# design.net
KiCad netlist of a schematic drawn in Altium Designer
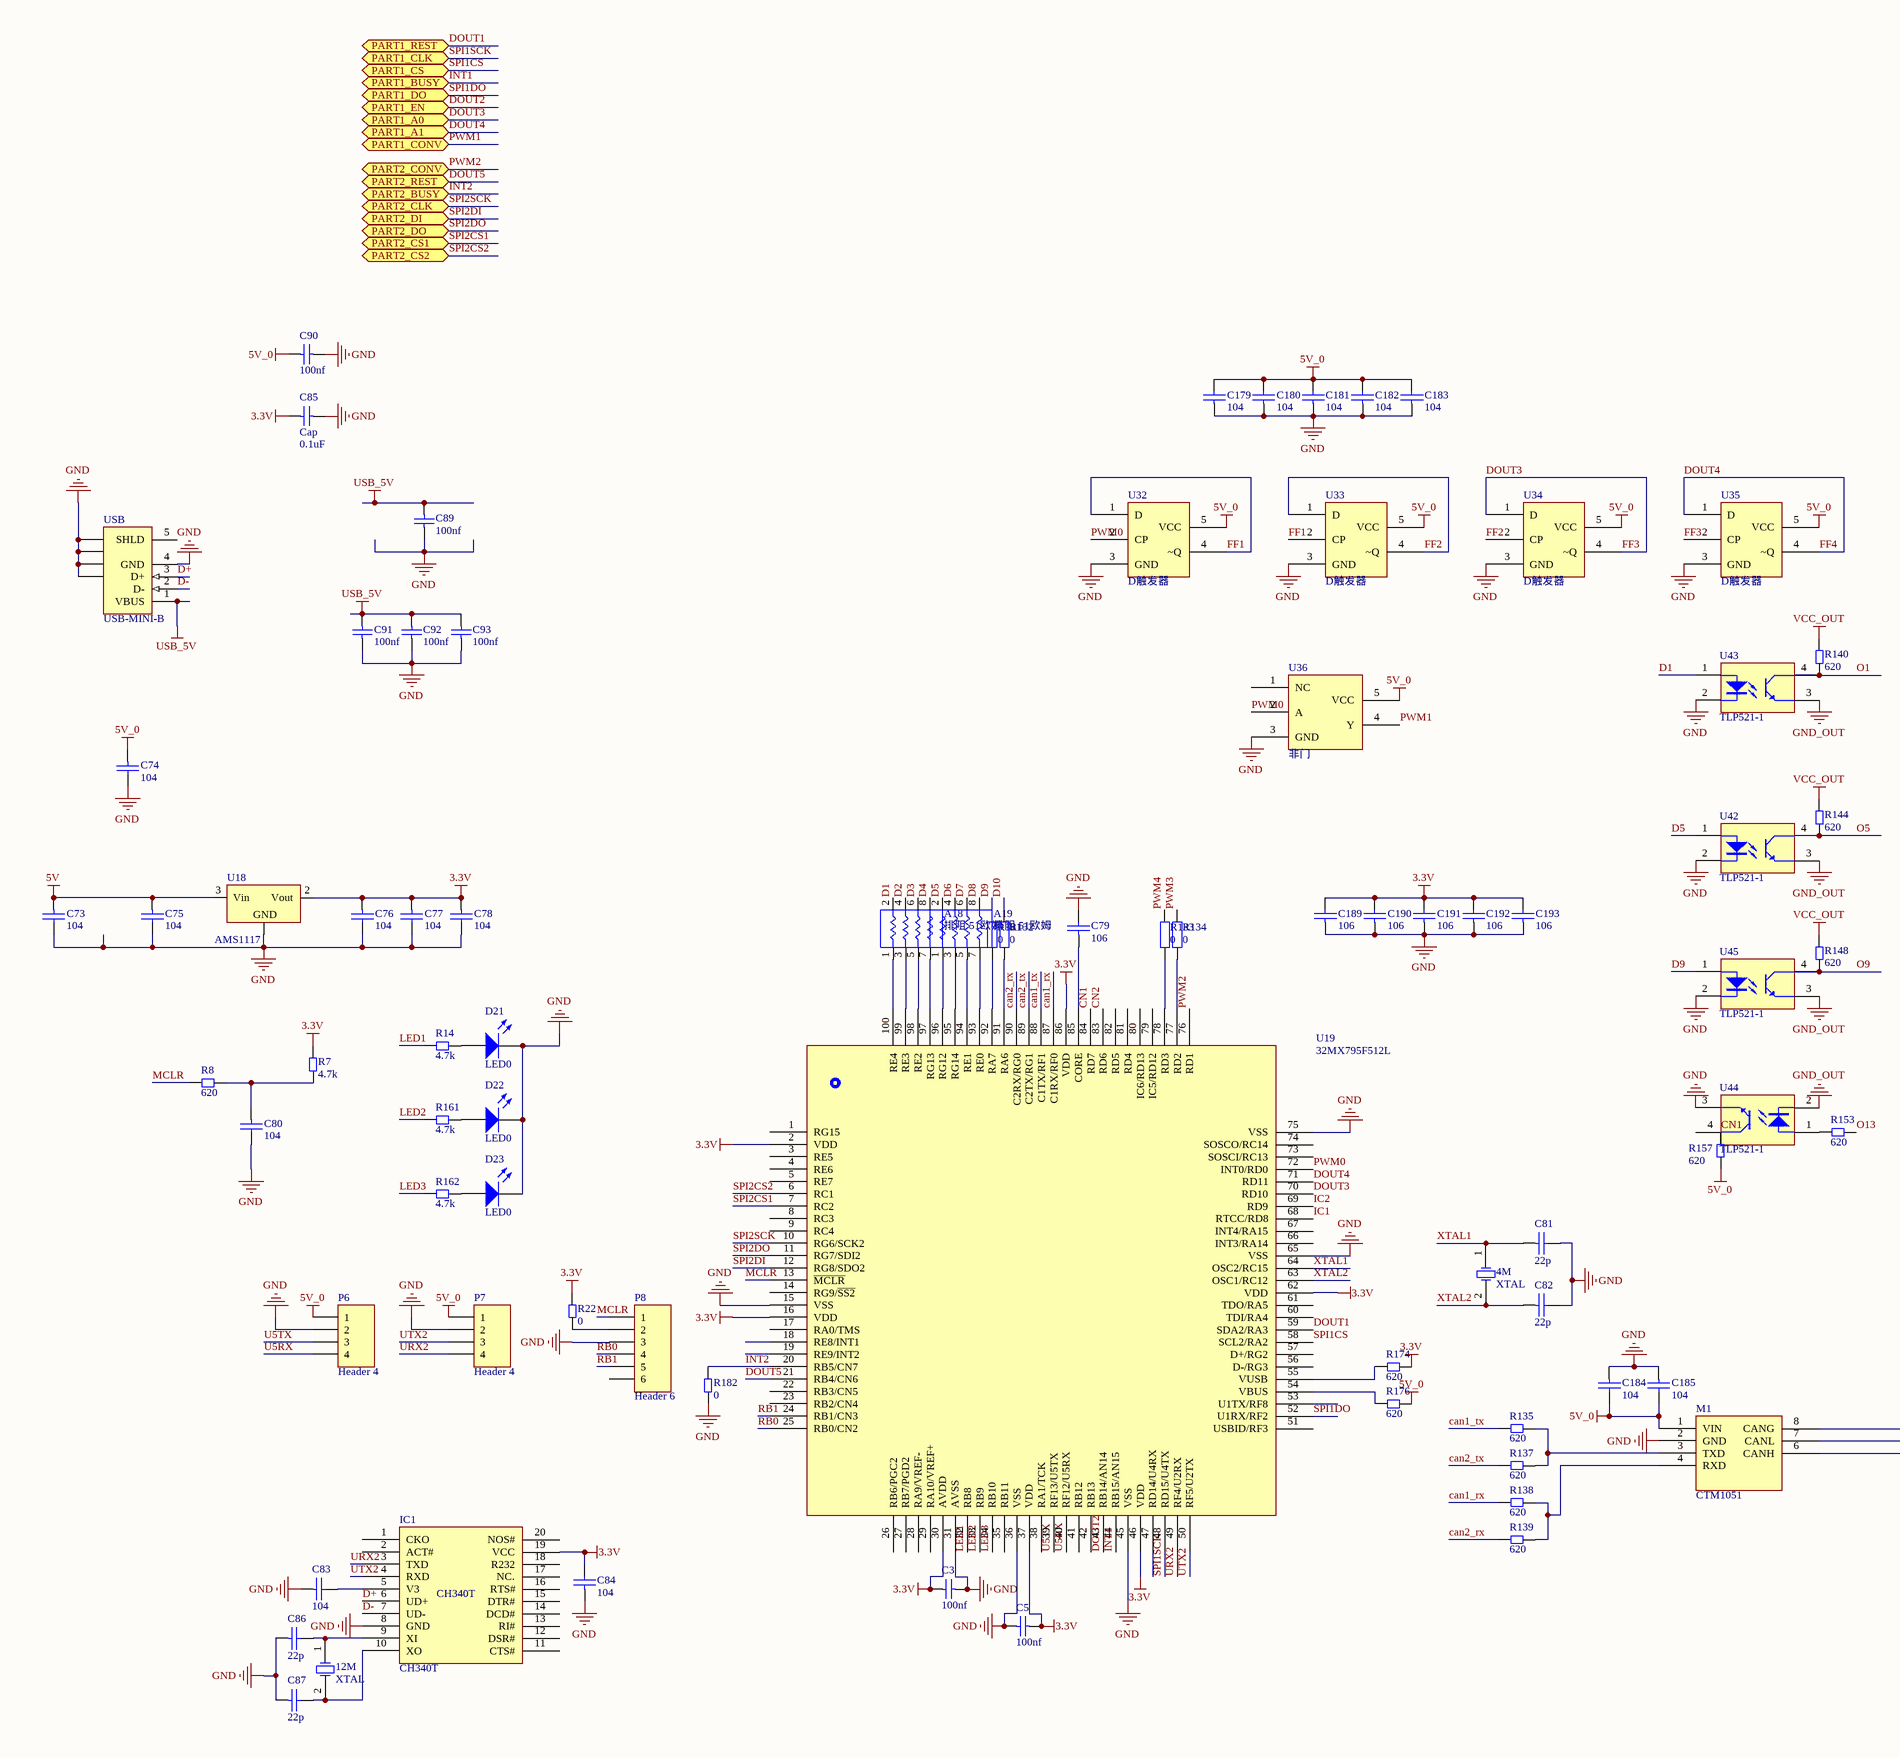
[diagram p0: 数字部分.SchDoc, left]
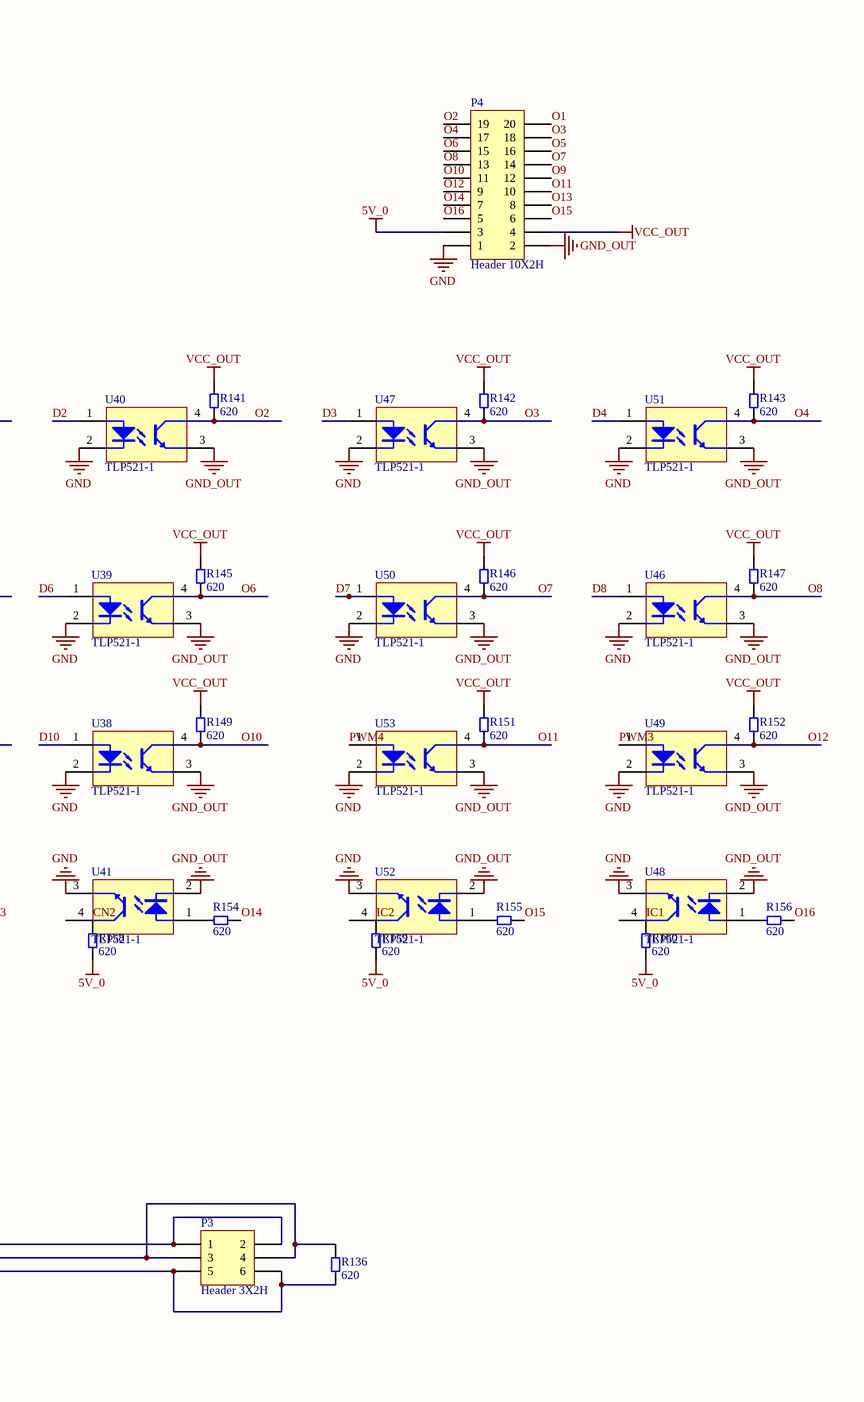
[diagram p1: 数字部分.SchDoc, right]

(export (version "E")
  (design (tool "Eeschema 10.0.6"))
  (components
    (comp (ref "4M")
      (value "XTAL")
      (footprint "5032-xtal")
      (description "Crystal Oscillator")
      (fields (field (name "PUBLISHER") "Altium Limited"))
      (libsource (lib "Miscellaneous Devices") (part "XTAL"))
    )
    (comp (ref "12M")
      (value "XTAL")
      (footprint "5032-xtal")
      (description "Crystal Oscillator")
      (fields (field (name "PUBLISHER") "Altium Limited"))
      (libsource (lib "Miscellaneous Devices") (part "XTAL"))
    )
    (comp (ref "A18")
      (value "排阻 51欧姆")
      (footprint "RCA03-4D")
      (libsource (lib "AD7606V23A") (part "RESPACK5"))
    )
    (comp (ref "A19")
      (value "排阻 51欧姆")
      (footprint "RCA03-4D")
      (libsource (lib "AD7606V23A") (part "RESPACK5"))
    )
    (comp (ref "C3")
      (value "100nf")
      (footprint "0805C")
      (description "Capacitor")
      (fields (field (name "Comment") "Cap") (field (name "PUBLISHER") "Altium Limited"))
      (libsource (lib "Miscellaneous Devices") (part "Cap"))
    )
    (comp (ref "C5")
      (value "100nf")
      (footprint "0805C")
      (description "Capacitor")
      (fields (field (name "Comment") "Cap") (field (name "PUBLISHER") "Altium Limited"))
      (libsource (lib "Miscellaneous Devices") (part "Cap"))
    )
    (comp (ref "C73")
      (value "104")
      (footprint "0805C")
      (description "Capacitor")
      (libsource (lib "Miscellaneous Devices") (part "CAP"))
    )
    (comp (ref "C74")
      (value "104")
      (footprint "0805C")
      (description "Capacitor")
      (libsource (lib "Miscellaneous Devices") (part "CAP"))
    )
    (comp (ref "C75")
      (value "104")
      (footprint "0805C")
      (description "Capacitor")
      (libsource (lib "Miscellaneous Devices") (part "CAP"))
    )
    (comp (ref "C76")
      (value "104")
      (footprint "0805C")
      (description "Capacitor")
      (libsource (lib "Miscellaneous Devices") (part "CAP"))
    )
    (comp (ref "C77")
      (value "104")
      (footprint "0805C")
      (description "Capacitor")
      (libsource (lib "Miscellaneous Devices") (part "CAP"))
    )
    (comp (ref "C78")
      (value "104")
      (footprint "0805C")
      (description "Capacitor")
      (libsource (lib "Miscellaneous Devices") (part "CAP"))
    )
    (comp (ref "C79")
      (value "106")
      (footprint "0805C")
      (description "Capacitor")
      (libsource (lib "Miscellaneous Devices") (part "CAP"))
    )
    (comp (ref "C80")
      (value "104")
      (footprint "0805C")
      (description "Capacitor")
      (libsource (lib "Miscellaneous Devices") (part "CAP"))
    )
    (comp (ref "C81")
      (value "22p")
      (footprint "0805C")
      (description "Capacitor")
      (libsource (lib "Miscellaneous Devices") (part "CAP"))
    )
    (comp (ref "C82")
      (value "22p")
      (footprint "0805C")
      (description "Capacitor")
      (libsource (lib "Miscellaneous Devices") (part "CAP"))
    )
    (comp (ref "C83")
      (value "104")
      (footprint "0805C")
      (description "Capacitor")
      (libsource (lib "Miscellaneous Devices") (part "CAP"))
    )
    (comp (ref "C84")
      (value "104")
      (footprint "0805C")
      (description "Capacitor")
      (libsource (lib "Miscellaneous Devices") (part "CAP"))
    )
    (comp (ref "C85")
      (value "Cap")
      (footprint "0805C")
      (description "Capacitor (Semiconductor SIM Model)")
      (fields (field (name "ALTIUM_VALUE") "0.1uF") (field (name "PUBLISHER") "Altium Limited"))
      (libsource (lib "Miscellaneous Devices") (part "Cap Semi"))
    )
    (comp (ref "C86")
      (value "22p")
      (footprint "0805C")
      (description "Capacitor")
      (libsource (lib "Miscellaneous Devices") (part "CAP"))
    )
    (comp (ref "C87")
      (value "22p")
      (footprint "0805C")
      (description "Capacitor")
      (libsource (lib "Miscellaneous Devices") (part "CAP"))
    )
    (comp (ref "C89")
      (value "100nf")
      (footprint "1812-C")
      (description "Capacitor")
      (fields (field (name "Comment") "Cap") (field (name "PUBLISHER") "Altium Limited"))
      (libsource (lib "Miscellaneous Devices") (part "Cap"))
    )
    (comp (ref "C90")
      (value "100nf")
      (footprint "0805C")
      (description "Capacitor")
      (fields (field (name "Comment") "Cap") (field (name "PUBLISHER") "Altium Limited"))
      (libsource (lib "Miscellaneous Devices") (part "Cap"))
    )
    (comp (ref "C91")
      (value "100nf")
      (footprint "0805C")
      (description "Capacitor")
      (fields (field (name "Comment") "Cap") (field (name "PUBLISHER") "Altium Limited"))
      (libsource (lib "Miscellaneous Devices") (part "Cap"))
    )
    (comp (ref "C92")
      (value "100nf")
      (footprint "0805C")
      (description "Capacitor")
      (fields (field (name "Comment") "Cap") (field (name "PUBLISHER") "Altium Limited"))
      (libsource (lib "Miscellaneous Devices") (part "Cap"))
    )
    (comp (ref "C93")
      (value "100nf")
      (footprint "0805C")
      (description "Capacitor")
      (fields (field (name "Comment") "Cap") (field (name "PUBLISHER") "Altium Limited"))
      (libsource (lib "Miscellaneous Devices") (part "Cap"))
    )
    (comp (ref "C179")
      (value "104")
      (footprint "0805C")
      (description "Capacitor")
      (libsource (lib "Miscellaneous Devices") (part "CAP"))
    )
    (comp (ref "C180")
      (value "104")
      (footprint "0805C")
      (description "Capacitor")
      (libsource (lib "Miscellaneous Devices") (part "CAP"))
    )
    (comp (ref "C181")
      (value "104")
      (footprint "0805C")
      (description "Capacitor")
      (libsource (lib "Miscellaneous Devices") (part "CAP"))
    )
    (comp (ref "C182")
      (value "104")
      (footprint "0805C")
      (description "Capacitor")
      (libsource (lib "Miscellaneous Devices") (part "CAP"))
    )
    (comp (ref "C183")
      (value "104")
      (footprint "0805C")
      (description "Capacitor")
      (libsource (lib "Miscellaneous Devices") (part "CAP"))
    )
    (comp (ref "C184")
      (value "104")
      (footprint "0805C")
      (description "Capacitor")
      (libsource (lib "Miscellaneous Devices") (part "CAP"))
    )
    (comp (ref "C185")
      (value "104")
      (footprint "0805C")
      (description "Capacitor")
      (libsource (lib "Miscellaneous Devices") (part "CAP"))
    )
    (comp (ref "C189")
      (value "106")
      (footprint "0805C")
      (description "Capacitor")
      (libsource (lib "Miscellaneous Devices") (part "CAP"))
    )
    (comp (ref "C190")
      (value "106")
      (footprint "0805C")
      (description "Capacitor")
      (libsource (lib "Miscellaneous Devices") (part "CAP"))
    )
    (comp (ref "C191")
      (value "106")
      (footprint "0805C")
      (description "Capacitor")
      (libsource (lib "Miscellaneous Devices") (part "CAP"))
    )
    (comp (ref "C192")
      (value "106")
      (footprint "0805C")
      (description "Capacitor")
      (libsource (lib "Miscellaneous Devices") (part "CAP"))
    )
    (comp (ref "C193")
      (value "106")
      (footprint "0805C")
      (description "Capacitor")
      (libsource (lib "Miscellaneous Devices") (part "CAP"))
    )
    (comp (ref "D21")
      (value "LED0")
      (footprint "0805C")
      (description "Typical INFRARED GaAs LED")
      (fields (field (name "PUBLISHER") "Altium Limited"))
      (libsource (lib "Miscellaneous Devices") (part "LED0"))
    )
    (comp (ref "D22")
      (value "LED0")
      (footprint "0805C")
      (description "Typical INFRARED GaAs LED")
      (fields (field (name "PUBLISHER") "Altium Limited"))
      (libsource (lib "Miscellaneous Devices") (part "LED0"))
    )
    (comp (ref "D23")
      (value "LED0")
      (footprint "0805C")
      (description "Typical INFRARED GaAs LED")
      (fields (field (name "PUBLISHER") "Altium Limited"))
      (libsource (lib "Miscellaneous Devices") (part "LED0"))
    )
    (comp (ref "IC1") (value "CH340T") (footprint "TSSOP20") (libsource (lib "ic_lib") (part "CH340T")))
    (comp (ref "M1") (value "CTM1051") (footprint "CTM1051") (libsource (lib "ic_lib") (part "CTM1051")))
    (comp (ref "P3")
      (value "Header 3X2H")
      (footprint "3.81MM-3P*2")
      (description "Header, 3-Pin, Dual row, Right Angle")
      (fields (field (name "PUBLISHER") "Altium Limited"))
      (libsource (lib "Miscellaneous Connectors") (part "Header 3X2H"))
    )
    (comp (ref "P4")
      (value "Header 10X2H")
      (footprint "20P牛角")
      (description "Header, 10-Pin, Dual row, Right Angle")
      (fields (field (name "PUBLISHER") "Altium Limited"))
      (libsource (lib "Miscellaneous Connectors") (part "Header 10X2H"))
    )
    (comp (ref "P6")
      (value "Header 4")
      (footprint "PH2.0 D-L-4P")
      (description "Header, 4-Pin")
      (fields (field (name "PUBLISHER") "Altium Limited"))
      (libsource (lib "Miscellaneous Connectors") (part "Header 4"))
    )
    (comp (ref "P7")
      (value "Header 4")
      (footprint "PH2.0 D-L-4P")
      (description "Header, 4-Pin")
      (fields (field (name "PUBLISHER") "Altium Limited"))
      (libsource (lib "Miscellaneous Connectors") (part "Header 4"))
    )
    (comp (ref "P8")
      (value "Header 6")
      (footprint "PH2.0 D-L-6P")
      (description "Header, 6-Pin")
      (fields (field (name "PUBLISHER") "Altium Limited"))
      (libsource (lib "Miscellaneous Connectors") (part "Header 6"))
    )
    (comp (ref "R7")
      (value "4.7k")
      (footprint "0805R")
      (libsource (lib "Miscellaneous Devices") (part "RES2"))
    )
    (comp (ref "R8")
      (value "620")
      (footprint "0805R")
      (libsource (lib "Miscellaneous Devices") (part "RES2"))
    )
    (comp (ref "R14")
      (value "4.7k")
      (footprint "0805R")
      (libsource (lib "Miscellaneous Devices") (part "RES2"))
    )
    (comp (ref "R22") (value "0") (footprint "0805R") (libsource (lib "Miscellaneous Devices") (part "RES2")))
    (comp (ref "R131")
      (value "0")
      (footprint "0603AR")
      (description "Resistor")
      (fields (field (name "Comment") "Res2") (field (name "PUBLISHER") "Altium Limited"))
      (libsource (lib "Miscellaneous Devices") (part "Res2"))
    )
    (comp (ref "R132")
      (value "0")
      (footprint "0603AR")
      (description "Resistor")
      (fields (field (name "Comment") "Res2") (field (name "PUBLISHER") "Altium Limited"))
      (libsource (lib "Miscellaneous Devices") (part "Res2"))
    )
    (comp (ref "R133")
      (value "0")
      (footprint "0603AR")
      (description "Resistor")
      (fields (field (name "Comment") "Res2") (field (name "PUBLISHER") "Altium Limited"))
      (libsource (lib "Miscellaneous Devices") (part "Res2"))
    )
    (comp (ref "R134")
      (value "0")
      (footprint "0603AR")
      (description "Resistor")
      (fields (field (name "Comment") "Res2") (field (name "PUBLISHER") "Altium Limited"))
      (libsource (lib "Miscellaneous Devices") (part "Res2"))
    )
    (comp (ref "R135")
      (value "620")
      (footprint "0805R")
      (libsource (lib "Miscellaneous Devices") (part "RES2"))
    )
    (comp (ref "R136")
      (value "620")
      (footprint "FB1206")
      (libsource (lib "Miscellaneous Devices") (part "RES2"))
    )
    (comp (ref "R137")
      (value "620")
      (footprint "0805R")
      (libsource (lib "Miscellaneous Devices") (part "RES2"))
    )
    (comp (ref "R138")
      (value "620")
      (footprint "0805R")
      (libsource (lib "Miscellaneous Devices") (part "RES2"))
    )
    (comp (ref "R139")
      (value "620")
      (footprint "0805R")
      (libsource (lib "Miscellaneous Devices") (part "RES2"))
    )
    (comp (ref "R140")
      (value "620")
      (footprint "0805R")
      (libsource (lib "Miscellaneous Devices") (part "RES2"))
    )
    (comp (ref "R141")
      (value "620")
      (footprint "0805R")
      (libsource (lib "Miscellaneous Devices") (part "RES2"))
    )
    (comp (ref "R142")
      (value "620")
      (footprint "0805R")
      (libsource (lib "Miscellaneous Devices") (part "RES2"))
    )
    (comp (ref "R143")
      (value "620")
      (footprint "0805R")
      (libsource (lib "Miscellaneous Devices") (part "RES2"))
    )
    (comp (ref "R144")
      (value "620")
      (footprint "0805R")
      (libsource (lib "Miscellaneous Devices") (part "RES2"))
    )
    (comp (ref "R145")
      (value "620")
      (footprint "0805R")
      (libsource (lib "Miscellaneous Devices") (part "RES2"))
    )
    (comp (ref "R146")
      (value "620")
      (footprint "0805R")
      (libsource (lib "Miscellaneous Devices") (part "RES2"))
    )
    (comp (ref "R147")
      (value "620")
      (footprint "0805R")
      (libsource (lib "Miscellaneous Devices") (part "RES2"))
    )
    (comp (ref "R148")
      (value "620")
      (footprint "0805R")
      (libsource (lib "Miscellaneous Devices") (part "RES2"))
    )
    (comp (ref "R149")
      (value "620")
      (footprint "0805R")
      (libsource (lib "Miscellaneous Devices") (part "RES2"))
    )
    (comp (ref "R151")
      (value "620")
      (footprint "0805R")
      (libsource (lib "Miscellaneous Devices") (part "RES2"))
    )
    (comp (ref "R152")
      (value "620")
      (footprint "0805R")
      (libsource (lib "Miscellaneous Devices") (part "RES2"))
    )
    (comp (ref "R153")
      (value "620")
      (footprint "0805R")
      (libsource (lib "Miscellaneous Devices") (part "RES2"))
    )
    (comp (ref "R154")
      (value "620")
      (footprint "0805R")
      (libsource (lib "Miscellaneous Devices") (part "RES2"))
    )
    (comp (ref "R155")
      (value "620")
      (footprint "0805R")
      (libsource (lib "Miscellaneous Devices") (part "RES2"))
    )
    (comp (ref "R156")
      (value "620")
      (footprint "0805R")
      (libsource (lib "Miscellaneous Devices") (part "RES2"))
    )
    (comp (ref "R157")
      (value "620")
      (footprint "0805R")
      (libsource (lib "Miscellaneous Devices") (part "RES2"))
    )
    (comp (ref "R158")
      (value "620")
      (footprint "0805R")
      (libsource (lib "Miscellaneous Devices") (part "RES2"))
    )
    (comp (ref "R159")
      (value "620")
      (footprint "0805R")
      (libsource (lib "Miscellaneous Devices") (part "RES2"))
    )
    (comp (ref "R160")
      (value "620")
      (footprint "0805R")
      (libsource (lib "Miscellaneous Devices") (part "RES2"))
    )
    (comp (ref "R161")
      (value "4.7k")
      (footprint "0805R")
      (libsource (lib "Miscellaneous Devices") (part "RES2"))
    )
    (comp (ref "R162")
      (value "4.7k")
      (footprint "0805R")
      (libsource (lib "Miscellaneous Devices") (part "RES2"))
    )
    (comp (ref "R174")
      (value "620")
      (footprint "0805R")
      (libsource (lib "Miscellaneous Devices") (part "RES2"))
    )
    (comp (ref "R176")
      (value "620")
      (footprint "0805R")
      (libsource (lib "Miscellaneous Devices") (part "RES2"))
    )
    (comp (ref "R182")
      (value "0")
      (footprint "0805R")
      (libsource (lib "Miscellaneous Devices") (part "RES2"))
    )
    (comp (ref "U18")
      (value "AMS1117")
      (footprint "_SOT-223")
      (description "LDO")
      (libsource (lib "IC") (part "AMS1117"))
    )
    (comp (ref "U19")
      (value "32MX795F512L")
      (footprint "TQFP100")
      (libsource (lib "客户元件") (part "32MX795F512L"))
    )
    (comp (ref "U32") (value "D触发器") (footprint "SOT-23-5") (libsource (lib "ic_lib") (part "D触发器")))
    (comp (ref "U33") (value "D触发器") (footprint "SOT-23-5") (libsource (lib "ic_lib") (part "D触发器")))
    (comp (ref "U34") (value "D触发器") (footprint "SOT-23-5") (libsource (lib "ic_lib") (part "D触发器")))
    (comp (ref "U35") (value "D触发器") (footprint "SOT-23-5") (libsource (lib "ic_lib") (part "D触发器")))
    (comp (ref "U36") (value "非门") (footprint "SOT-23-5") (libsource (lib "ic_lib") (part "非门")))
    (comp (ref "U38")
      (value "TLP521-1")
      (footprint "SOP4")
      (description "光耦")
      (libsource (lib "Personal_Accumulation_Sch") (part "TLP521-1"))
    )
    (comp (ref "U39")
      (value "TLP521-1")
      (footprint "SOP4")
      (description "光耦")
      (libsource (lib "Personal_Accumulation_Sch") (part "TLP521-1"))
    )
    (comp (ref "U40")
      (value "TLP521-1")
      (footprint "SOP4")
      (description "光耦")
      (libsource (lib "Personal_Accumulation_Sch") (part "TLP521-1"))
    )
    (comp (ref "U41")
      (value "TLP521-1")
      (footprint "SOP4")
      (description "光耦")
      (libsource (lib "") (part "TLP521-1_1"))
    )
    (comp (ref "U42")
      (value "TLP521-1")
      (footprint "SOP4")
      (description "光耦")
      (libsource (lib "Personal_Accumulation_Sch") (part "TLP521-1"))
    )
    (comp (ref "U43")
      (value "TLP521-1")
      (footprint "SOP4")
      (description "光耦")
      (libsource (lib "Personal_Accumulation_Sch") (part "TLP521-1"))
    )
    (comp (ref "U44")
      (value "TLP521-1")
      (footprint "SOP4")
      (description "光耦")
      (libsource (lib "") (part "TLP521-1_1"))
    )
    (comp (ref "U45")
      (value "TLP521-1")
      (footprint "SOP4")
      (description "光耦")
      (libsource (lib "Personal_Accumulation_Sch") (part "TLP521-1"))
    )
    (comp (ref "U46")
      (value "TLP521-1")
      (footprint "SOP4")
      (description "光耦")
      (libsource (lib "Personal_Accumulation_Sch") (part "TLP521-1"))
    )
    (comp (ref "U47")
      (value "TLP521-1")
      (footprint "SOP4")
      (description "光耦")
      (libsource (lib "Personal_Accumulation_Sch") (part "TLP521-1"))
    )
    (comp (ref "U48")
      (value "TLP521-1")
      (footprint "SOP4")
      (description "光耦")
      (libsource (lib "") (part "TLP521-1_1"))
    )
    (comp (ref "U49")
      (value "TLP521-1")
      (footprint "SOP4")
      (description "光耦")
      (libsource (lib "Personal_Accumulation_Sch") (part "TLP521-1"))
    )
    (comp (ref "U50")
      (value "TLP521-1")
      (footprint "SOP4")
      (description "光耦")
      (libsource (lib "Personal_Accumulation_Sch") (part "TLP521-1"))
    )
    (comp (ref "U51")
      (value "TLP521-1")
      (footprint "SOP4")
      (description "光耦")
      (libsource (lib "Personal_Accumulation_Sch") (part "TLP521-1"))
    )
    (comp (ref "U52")
      (value "TLP521-1")
      (footprint "SOP4")
      (description "光耦")
      (libsource (lib "") (part "TLP521-1_1"))
    )
    (comp (ref "U53")
      (value "TLP521-1")
      (footprint "SOP4")
      (description "光耦")
      (libsource (lib "Personal_Accumulation_Sch") (part "TLP521-1"))
    )
    (comp (ref "USB")
      (value "USB-MINI-B")
      (footprint "USB-MINI-B - 引脚加长")
      (description "USB 2.0, Right Angle, SMT, A Type, Receptacle, 5 Position, Black")
      (fields (field (name "PUBLISHER") "Altium Limited"))
      (libsource (lib "Sparks") (part "USB-MINI-B"))
    )
  )
  (nets
    (net (code "1") (name "/CN1") (class "Default")
      (node (ref "R157") (pin "1") (pinfunction "1_1") (pintype "passive"))
      (node (ref "U19") (pin "84") (pinfunction "RD7_84") (pintype "passive"))
      (node (ref "U44") (pin "4") (pinfunction "4_4") (pintype "passive"))
    )
    (net (code "2") (name "/CN2") (class "Default")
      (node (ref "R158") (pin "1") (pinfunction "1_1") (pintype "passive"))
      (node (ref "U19") (pin "83") (pinfunction "RD6_83") (pintype "passive"))
      (node (ref "U41") (pin "4") (pinfunction "4_4") (pintype "passive"))
    )
    (net (code "3") (name "/D+") (class "Default")
      (node (ref "IC1") (pin "6") (pinfunction "UD+_6") (pintype "passive"))
      (node (ref "USB") (pin "3") (pinfunction "D+_3") (pintype "input"))
    )
    (net (code "4") (name "/D-") (class "Default")
      (node (ref "IC1") (pin "7") (pinfunction "UD-_7") (pintype "passive"))
      (node (ref "USB") (pin "2") (pinfunction "D-_2") (pintype "input"))
    )
    (net (code "5") (name "/D1") (class "Default")
      (node (ref "A18") (pin "2") (pinfunction "2_2") (pintype "passive"))
      (node (ref "U43") (pin "1") (pinfunction "1_1") (pintype "passive"))
    )
    (net (code "6") (name "/D2") (class "Default")
      (node (ref "A18") (pin "4") (pinfunction "4_4") (pintype "passive"))
      (node (ref "U40") (pin "1") (pinfunction "1_1") (pintype "passive"))
    )
    (net (code "7") (name "/D3") (class "Default")
      (node (ref "A18") (pin "6") (pinfunction "8_6") (pintype "passive"))
      (node (ref "U47") (pin "1") (pinfunction "1_1") (pintype "passive"))
    )
    (net (code "8") (name "/D4") (class "Default")
      (node (ref "A18") (pin "8") (pinfunction "8_8") (pintype "passive"))
      (node (ref "U51") (pin "1") (pinfunction "1_1") (pintype "passive"))
    )
    (net (code "9") (name "/D5") (class "Default")
      (node (ref "A19") (pin "2") (pinfunction "2_2") (pintype "passive"))
      (node (ref "U42") (pin "1") (pinfunction "1_1") (pintype "passive"))
    )
    (net (code "10") (name "/D6") (class "Default")
      (node (ref "A19") (pin "4") (pinfunction "4_4") (pintype "passive"))
      (node (ref "U39") (pin "1") (pinfunction "1_1") (pintype "passive"))
    )
    (net (code "11") (name "/D7") (class "Default")
      (node (ref "A19") (pin "6") (pinfunction "8_6") (pintype "passive"))
      (node (ref "U50") (pin "1") (pinfunction "1_1") (pintype "passive"))
    )
    (net (code "12") (name "/D8") (class "Default")
      (node (ref "A19") (pin "8") (pinfunction "8_8") (pintype "passive"))
      (node (ref "U46") (pin "1") (pinfunction "1_1") (pintype "passive"))
    )
    (net (code "13") (name "/D9") (class "Default")
      (node (ref "R131") (pin "1") (pinfunction "1_1") (pintype "passive"))
      (node (ref "U45") (pin "1") (pinfunction "1_1") (pintype "passive"))
    )
    (net (code "14") (name "/D10") (class "Default")
      (node (ref "R132") (pin "1") (pinfunction "1_1") (pintype "passive"))
      (node (ref "U38") (pin "1") (pinfunction "1_1") (pintype "passive"))
    )
    (net (code "15") (name "/DOUT1") (class "Default")
      (node (ref "U19") (pin "59") (pinfunction "SDA2/RA3_59") (pintype "passive"))
    )
    (net (code "16") (name "/DOUT2") (class "Default")
      (node (ref "U19") (pin "43") (pinfunction "RB14/AN14_43") (pintype "passive"))
    )
    (net (code "17") (name "/DOUT3") (class "Default")
      (node (ref "U19") (pin "70") (pinfunction "RD10_70") (pintype "passive"))
      (node (ref "U34") (pin "1") (pinfunction "D_1") (pintype "passive"))
      (node (ref "U34") (pin "4") (pinfunction "~Q_4") (pintype "passive"))
      (node (ref "U35") (pin "2") (pinfunction "CP_2") (pintype "passive"))
    )
    (net (code "18") (name "/DOUT4") (class "Default")
      (node (ref "U19") (pin "71") (pinfunction "RD11_71") (pintype "passive"))
      (node (ref "U35") (pin "1") (pinfunction "D_1") (pintype "passive"))
      (node (ref "U35") (pin "4") (pinfunction "~Q_4") (pintype "passive"))
    )
    (net (code "19") (name "/DOUT5") (class "Default")
      (node (ref "U19") (pin "21") (pinfunction "RB4/CN6_21") (pintype "passive"))
    )
    (net (code "20") (name "/FF1") (class "Default")
      (node (ref "U32") (pin "1") (pinfunction "D_1") (pintype "passive"))
      (node (ref "U32") (pin "4") (pinfunction "~Q_4") (pintype "passive"))
      (node (ref "U33") (pin "2") (pinfunction "CP_2") (pintype "passive"))
    )
    (net (code "21") (name "/FF2") (class "Default")
      (node (ref "U33") (pin "1") (pinfunction "D_1") (pintype "passive"))
      (node (ref "U33") (pin "4") (pinfunction "~Q_4") (pintype "passive"))
      (node (ref "U34") (pin "2") (pinfunction "CP_2") (pintype "passive"))
    )
    (net (code "22") (name "/IC1") (class "Default")
      (node (ref "R160") (pin "1") (pinfunction "1_1") (pintype "passive"))
      (node (ref "U19") (pin "68") (pinfunction "RTCC/RD8_68") (pintype "passive"))
      (node (ref "U48") (pin "4") (pinfunction "4_4") (pintype "passive"))
    )
    (net (code "23") (name "/IC2") (class "Default")
      (node (ref "R159") (pin "1") (pinfunction "1_1") (pintype "passive"))
      (node (ref "U19") (pin "69") (pinfunction "RD9_69") (pintype "passive"))
      (node (ref "U52") (pin "4") (pinfunction "4_4") (pintype "passive"))
    )
    (net (code "24") (name "/INT1") (class "Default")
      (node (ref "U19") (pin "44") (pinfunction "RB15/AN15_44") (pintype "passive"))
    )
    (net (code "25") (name "/INT2") (class "Default")
      (node (ref "R182") (pin "2") (pinfunction "2_2") (pintype "passive"))
      (node (ref "U19") (pin "20") (pinfunction "RB5/CN7_20") (pintype "passive"))
    )
    (net (code "26") (name "/LED1") (class "Default")
      (node (ref "R14") (pin "1") (pinfunction "1_1") (pintype "passive"))
      (node (ref "U19") (pin "32") (pinfunction "RB8_32") (pintype "passive"))
    )
    (net (code "27") (name "/LED2") (class "Default")
      (node (ref "R161") (pin "1") (pinfunction "1_1") (pintype "passive"))
      (node (ref "U19") (pin "33") (pinfunction "RB9_33") (pintype "passive"))
    )
    (net (code "28") (name "/LED3") (class "Default")
      (node (ref "R162") (pin "1") (pinfunction "1_1") (pintype "passive"))
      (node (ref "U19") (pin "34") (pinfunction "RB10_34") (pintype "passive"))
    )
    (net (code "29") (name "/MCLR") (class "Default")
      (node (ref "P8") (pin "1") (pinfunction "1_1") (pintype "passive"))
      (node (ref "R8") (pin "1") (pinfunction "1_1") (pintype "passive"))
      (node (ref "U19") (pin "13") (pinfunction "~{MCLR}_13") (pintype "passive"))
    )
    (net (code "30") (name "/O1") (class "Default")
      (node (ref "P4") (pin "20") (pinfunction "20_20") (pintype "passive"))
      (node (ref "R140") (pin "1") (pinfunction "1_1") (pintype "passive"))
      (node (ref "U43") (pin "4") (pinfunction "4_4") (pintype "passive"))
    )
    (net (code "31") (name "/O2") (class "Default")
      (node (ref "P4") (pin "19") (pinfunction "19_19") (pintype "passive"))
      (node (ref "R141") (pin "1") (pinfunction "1_1") (pintype "passive"))
      (node (ref "U40") (pin "4") (pinfunction "4_4") (pintype "passive"))
    )
    (net (code "32") (name "/O3") (class "Default")
      (node (ref "P4") (pin "18") (pinfunction "18_18") (pintype "passive"))
      (node (ref "R142") (pin "1") (pinfunction "1_1") (pintype "passive"))
      (node (ref "U47") (pin "4") (pinfunction "4_4") (pintype "passive"))
    )
    (net (code "33") (name "/O4") (class "Default")
      (node (ref "P4") (pin "17") (pinfunction "17_17") (pintype "passive"))
      (node (ref "R143") (pin "1") (pinfunction "1_1") (pintype "passive"))
      (node (ref "U51") (pin "4") (pinfunction "4_4") (pintype "passive"))
    )
    (net (code "34") (name "/O5") (class "Default")
      (node (ref "P4") (pin "16") (pinfunction "16_16") (pintype "passive"))
      (node (ref "R144") (pin "1") (pinfunction "1_1") (pintype "passive"))
      (node (ref "U42") (pin "4") (pinfunction "4_4") (pintype "passive"))
    )
    (net (code "35") (name "/O6") (class "Default")
      (node (ref "P4") (pin "15") (pinfunction "15_15") (pintype "passive"))
      (node (ref "R145") (pin "1") (pinfunction "1_1") (pintype "passive"))
      (node (ref "U39") (pin "4") (pinfunction "4_4") (pintype "passive"))
    )
    (net (code "36") (name "/O7") (class "Default")
      (node (ref "P4") (pin "14") (pinfunction "14_14") (pintype "passive"))
      (node (ref "R146") (pin "1") (pinfunction "1_1") (pintype "passive"))
      (node (ref "U50") (pin "4") (pinfunction "4_4") (pintype "passive"))
    )
    (net (code "37") (name "/O8") (class "Default")
      (node (ref "P4") (pin "13") (pinfunction "13_13") (pintype "passive"))
      (node (ref "R147") (pin "1") (pinfunction "1_1") (pintype "passive"))
      (node (ref "U46") (pin "4") (pinfunction "4_4") (pintype "passive"))
    )
    (net (code "38") (name "/O9") (class "Default")
      (node (ref "P4") (pin "12") (pinfunction "12_12") (pintype "passive"))
      (node (ref "R148") (pin "1") (pinfunction "1_1") (pintype "passive"))
      (node (ref "U45") (pin "4") (pinfunction "4_4") (pintype "passive"))
    )
    (net (code "39") (name "/O10") (class "Default")
      (node (ref "P4") (pin "11") (pinfunction "11_11") (pintype "passive"))
      (node (ref "R149") (pin "1") (pinfunction "1_1") (pintype "passive"))
      (node (ref "U38") (pin "4") (pinfunction "4_4") (pintype "passive"))
    )
    (net (code "40") (name "/O11") (class "Default")
      (node (ref "P4") (pin "10") (pinfunction "10_10") (pintype "passive"))
      (node (ref "R151") (pin "1") (pinfunction "1_1") (pintype "passive"))
      (node (ref "U53") (pin "4") (pinfunction "4_4") (pintype "passive"))
    )
    (net (code "41") (name "/O12") (class "Default")
      (node (ref "P4") (pin "9") (pinfunction "9_9") (pintype "passive"))
      (node (ref "R152") (pin "1") (pinfunction "1_1") (pintype "passive"))
      (node (ref "U49") (pin "4") (pinfunction "4_4") (pintype "passive"))
    )
    (net (code "42") (name "/O13") (class "Default")
      (node (ref "P4") (pin "8") (pinfunction "8_8") (pintype "passive"))
      (node (ref "R153") (pin "2") (pinfunction "2_2") (pintype "passive"))
    )
    (net (code "43") (name "/O14") (class "Default")
      (node (ref "P4") (pin "7") (pinfunction "7_7") (pintype "passive"))
      (node (ref "R154") (pin "2") (pinfunction "2_2") (pintype "passive"))
    )
    (net (code "44") (name "/O15") (class "Default")
      (node (ref "P4") (pin "6") (pinfunction "6_6") (pintype "passive"))
      (node (ref "R155") (pin "2") (pinfunction "2_2") (pintype "passive"))
    )
    (net (code "45") (name "/O16") (class "Default")
      (node (ref "P4") (pin "5") (pinfunction "5_5") (pintype "passive"))
      (node (ref "R156") (pin "2") (pinfunction "2_2") (pintype "passive"))
    )
    (net (code "46") (name "/PWM0") (class "Default")
      (node (ref "U19") (pin "72") (pinfunction "INT0/RD0_72") (pintype "passive"))
      (node (ref "U32") (pin "2") (pinfunction "CP_2") (pintype "passive"))
      (node (ref "U36") (pin "2") (pinfunction "A_2") (pintype "passive"))
    )
    (net (code "47") (name "/PWM1") (class "Default")
      (node (ref "U36") (pin "4") (pinfunction "Y_4") (pintype "passive"))
    )
    (net (code "48") (name "/PWM2") (class "Default")
      (node (ref "U19") (pin "76") (pinfunction "RD1_76") (pintype "passive"))
    )
    (net (code "49") (name "/PWM3") (class "Default")
      (node (ref "R134") (pin "1") (pinfunction "1_1") (pintype "passive"))
      (node (ref "U49") (pin "1") (pinfunction "1_1") (pintype "passive"))
    )
    (net (code "50") (name "/PWM4") (class "Default")
      (node (ref "R133") (pin "1") (pinfunction "1_1") (pintype "passive"))
      (node (ref "U53") (pin "1") (pinfunction "1_1") (pintype "passive"))
    )
    (net (code "51") (name "/RB0") (class "Default")
      (node (ref "P8") (pin "4") (pinfunction "4_4") (pintype "passive"))
      (node (ref "U19") (pin "25") (pinfunction "RB0/CN2_25") (pintype "passive"))
    )
    (net (code "52") (name "/RB1") (class "Default")
      (node (ref "P8") (pin "5") (pinfunction "5_5") (pintype "passive"))
      (node (ref "U19") (pin "24") (pinfunction "RB1/CN3_24") (pintype "passive"))
    )
    (net (code "53") (name "/SPI1CS") (class "Default")
      (node (ref "U19") (pin "58") (pinfunction "SCL2/RA2_58") (pintype "passive"))
    )
    (net (code "54") (name "/SPI1DO") (class "Default")
      (node (ref "U19") (pin "52") (pinfunction "U1RX/RF2_52") (pintype "passive"))
    )
    (net (code "55") (name "/SPI1SCK") (class "Default")
      (node (ref "U19") (pin "48") (pinfunction "RD15/U4TX_48") (pintype "passive"))
    )
    (net (code "56") (name "/SPI2CS1") (class "Default")
      (node (ref "U19") (pin "7") (pinfunction "RC2_7") (pintype "passive"))
    )
    (net (code "57") (name "/SPI2CS2") (class "Default")
      (node (ref "U19") (pin "6") (pinfunction "RC1_6") (pintype "passive"))
    )
    (net (code "58") (name "/SPI2DI") (class "Default")
      (node (ref "U19") (pin "12") (pinfunction "RG8/SDO2_12") (pintype "passive"))
    )
    (net (code "59") (name "/SPI2DO") (class "Default")
      (node (ref "U19") (pin "11") (pinfunction "RG7/SDI2_11") (pintype "passive"))
    )
    (net (code "60") (name "/SPI2SCK") (class "Default")
      (node (ref "U19") (pin "10") (pinfunction "RG6/SCK2_10") (pintype "passive"))
    )
    (net (code "61") (name "/U5RX") (class "Default")
      (node (ref "P6") (pin "4") (pinfunction "4_4") (pintype "passive"))
      (node (ref "U19") (pin "40") (pinfunction "RF12/U5RX_40") (pintype "passive"))
    )
    (net (code "62") (name "/U5TX") (class "Default")
      (node (ref "P6") (pin "3") (pinfunction "3_3") (pintype "passive"))
      (node (ref "U19") (pin "39") (pinfunction "RF13/U5TX_39") (pintype "passive"))
    )
    (net (code "63") (name "/URX2") (class "Default")
      (node (ref "IC1") (pin "3") (pinfunction "TXD_3") (pintype "passive"))
      (node (ref "P7") (pin "4") (pinfunction "4_4") (pintype "passive"))
      (node (ref "U19") (pin "49") (pinfunction "RF4/U2RX_49") (pintype "passive"))
    )
    (net (code "64") (name "/UTX2") (class "Default")
      (node (ref "IC1") (pin "4") (pinfunction "RXD_4") (pintype "passive"))
      (node (ref "P7") (pin "3") (pinfunction "3_3") (pintype "passive"))
      (node (ref "U19") (pin "50") (pinfunction "RF5/U2TX_50") (pintype "passive"))
    )
    (net (code "65") (name "/XTAL1") (class "Default")
      (node (ref "4M") (pin "1") (pinfunction "OSC1_1") (pintype "passive"))
      (node (ref "C81") (pin "1") (pinfunction "1_1") (pintype "passive"))
      (node (ref "U19") (pin "64") (pinfunction "OSC2/RC15_64") (pintype "passive"))
    )
    (net (code "66") (name "/XTAL2") (class "Default")
      (node (ref "4M") (pin "2") (pinfunction "OSC2_2") (pintype "passive"))
      (node (ref "C82") (pin "1") (pinfunction "1_1") (pintype "passive"))
      (node (ref "U19") (pin "63") (pinfunction "OSC1/RC12_63") (pintype "passive"))
    )
    (net (code "67") (name "/can1_rx") (class "Default")
      (node (ref "R138") (pin "1") (pinfunction "1_1") (pintype "passive"))
      (node (ref "U19") (pin "87") (pinfunction "C1RX/RF0_87") (pintype "passive"))
    )
    (net (code "68") (name "/can1_tx") (class "Default")
      (node (ref "R135") (pin "1") (pinfunction "1_1") (pintype "passive"))
      (node (ref "U19") (pin "88") (pinfunction "C1TX/RF1_88") (pintype "passive"))
    )
    (net (code "69") (name "/can2_rx") (class "Default")
      (node (ref "R139") (pin "1") (pinfunction "1_1") (pintype "passive"))
      (node (ref "U19") (pin "90") (pinfunction "C2RX/RG0_90") (pintype "passive"))
    )
    (net (code "70") (name "/can2_tx") (class "Default")
      (node (ref "R137") (pin "1") (pinfunction "1_1") (pintype "passive"))
      (node (ref "U19") (pin "89") (pinfunction "C2TX/RG1_89") (pintype "passive"))
    )
    (net (code "71") (name "3.3V") (class "Default")
      (node (ref "C189") (pin "2") (pinfunction "2_2") (pintype "passive"))
      (node (ref "C190") (pin "2") (pinfunction "2_2") (pintype "passive"))
      (node (ref "C191") (pin "2") (pinfunction "2_2") (pintype "passive"))
      (node (ref "C192") (pin "2") (pinfunction "2_2") (pintype "passive"))
      (node (ref "C193") (pin "2") (pinfunction "2_2") (pintype "passive"))
      (node (ref "C3") (pin "2") (pinfunction "2_2") (pintype "passive"))
      (node (ref "C5") (pin "2") (pinfunction "2_2") (pintype "passive"))
      (node (ref "C76") (pin "1") (pinfunction "1_1") (pintype "passive"))
      (node (ref "C77") (pin "1") (pinfunction "1_1") (pintype "passive"))
      (node (ref "C78") (pin "1") (pinfunction "1_1") (pintype "passive"))
      (node (ref "C84") (pin "2") (pinfunction "2_2") (pintype "passive"))
      (node (ref "C85") (pin "2") (pinfunction "2_2") (pintype "passive"))
      (node (ref "IC1") (pin "19") (pinfunction "VCC_19") (pintype "passive"))
      (node (ref "R174") (pin "2") (pinfunction "2_2") (pintype "passive"))
      (node (ref "R22") (pin "2") (pinfunction "2_2") (pintype "passive"))
      (node (ref "R7") (pin "1") (pinfunction "1_1") (pintype "passive"))
      (node (ref "U18") (pin "2") (pinfunction "Vout_2") (pintype "passive"))
      (node (ref "U19") (pin "16") (pinfunction "VDD_16") (pintype "passive"))
      (node (ref "U19") (pin "2") (pinfunction "VDD_2") (pintype "passive"))
      (node (ref "U19") (pin "30") (pinfunction "AVDD_30") (pintype "passive"))
      (node (ref "U19") (pin "37") (pinfunction "VDD_37") (pintype "passive"))
      (node (ref "U19") (pin "46") (pinfunction "VDD_46") (pintype "passive"))
      (node (ref "U19") (pin "62") (pinfunction "VDD_62") (pintype "passive"))
      (node (ref "U19") (pin "86") (pinfunction "VDD_86") (pintype "passive"))
    )
    (net (code "72") (name "5V") (class "Default")
      (node (ref "C73") (pin "1") (pinfunction "1_1") (pintype "passive"))
      (node (ref "C75") (pin "1") (pinfunction "1_1") (pintype "passive"))
      (node (ref "U18") (pin "3") (pinfunction "Vin_3") (pintype "passive"))
    )
    (net (code "73") (name "5V_0") (class "Default")
      (node (ref "C179") (pin "2") (pinfunction "2_2") (pintype "passive"))
      (node (ref "C180") (pin "2") (pinfunction "2_2") (pintype "passive"))
      (node (ref "C181") (pin "2") (pinfunction "2_2") (pintype "passive"))
      (node (ref "C182") (pin "2") (pinfunction "2_2") (pintype "passive"))
      (node (ref "C183") (pin "2") (pinfunction "2_2") (pintype "passive"))
      (node (ref "C184") (pin "2") (pinfunction "2_2") (pintype "passive"))
      (node (ref "C185") (pin "2") (pinfunction "2_2") (pintype "passive"))
      (node (ref "C74") (pin "1") (pinfunction "1_1") (pintype "passive"))
      (node (ref "C90") (pin "2") (pinfunction "2_2") (pintype "passive"))
      (node (ref "M1") (pin "1") (pinfunction "VIN_1") (pintype "passive"))
      (node (ref "P4") (pin "3") (pinfunction "3_3") (pintype "passive"))
      (node (ref "P6") (pin "1") (pinfunction "1_1") (pintype "passive"))
      (node (ref "P7") (pin "1") (pinfunction "1_1") (pintype "passive"))
      (node (ref "R157") (pin "2") (pinfunction "2_2") (pintype "passive"))
      (node (ref "R158") (pin "2") (pinfunction "2_2") (pintype "passive"))
      (node (ref "R159") (pin "2") (pinfunction "2_2") (pintype "passive"))
      (node (ref "R160") (pin "2") (pinfunction "2_2") (pintype "passive"))
      (node (ref "R176") (pin "2") (pinfunction "2_2") (pintype "passive"))
      (node (ref "U32") (pin "5") (pinfunction "VCC_5") (pintype "passive"))
      (node (ref "U33") (pin "5") (pinfunction "VCC_5") (pintype "passive"))
      (node (ref "U34") (pin "5") (pinfunction "VCC_5") (pintype "passive"))
      (node (ref "U35") (pin "5") (pinfunction "VCC_5") (pintype "passive"))
      (node (ref "U36") (pin "5") (pinfunction "VCC_5") (pintype "passive"))
    )
    (net (code "74") (name "GND") (class "Default")
      (node (ref "C179") (pin "1") (pinfunction "1_1") (pintype "passive"))
      (node (ref "C180") (pin "1") (pinfunction "1_1") (pintype "passive"))
      (node (ref "C181") (pin "1") (pinfunction "1_1") (pintype "passive"))
      (node (ref "C182") (pin "1") (pinfunction "1_1") (pintype "passive"))
      (node (ref "C183") (pin "1") (pinfunction "1_1") (pintype "passive"))
      (node (ref "C184") (pin "1") (pinfunction "1_1") (pintype "passive"))
      (node (ref "C185") (pin "1") (pinfunction "1_1") (pintype "passive"))
      (node (ref "C189") (pin "1") (pinfunction "1_1") (pintype "passive"))
      (node (ref "C190") (pin "1") (pinfunction "1_1") (pintype "passive"))
      (node (ref "C191") (pin "1") (pinfunction "1_1") (pintype "passive"))
      (node (ref "C192") (pin "1") (pinfunction "1_1") (pintype "passive"))
      (node (ref "C193") (pin "1") (pinfunction "1_1") (pintype "passive"))
      (node (ref "C3") (pin "1") (pinfunction "1_1") (pintype "passive"))
      (node (ref "C5") (pin "1") (pinfunction "1_1") (pintype "passive"))
      (node (ref "C73") (pin "2") (pinfunction "2_2") (pintype "passive"))
      (node (ref "C74") (pin "2") (pinfunction "2_2") (pintype "passive"))
      (node (ref "C75") (pin "2") (pinfunction "2_2") (pintype "passive"))
      (node (ref "C76") (pin "2") (pinfunction "2_2") (pintype "passive"))
      (node (ref "C77") (pin "2") (pinfunction "2_2") (pintype "passive"))
      (node (ref "C78") (pin "2") (pinfunction "2_2") (pintype "passive"))
      (node (ref "C79") (pin "2") (pinfunction "2_2") (pintype "passive"))
      (node (ref "C80") (pin "2") (pinfunction "2_2") (pintype "passive"))
      (node (ref "C81") (pin "2") (pinfunction "2_2") (pintype "passive"))
      (node (ref "C82") (pin "2") (pinfunction "2_2") (pintype "passive"))
      (node (ref "C83") (pin "1") (pinfunction "1_1") (pintype "passive"))
      (node (ref "C84") (pin "1") (pinfunction "1_1") (pintype "passive"))
      (node (ref "C85") (pin "1") (pinfunction "1_1") (pintype "passive"))
      (node (ref "C86") (pin "1") (pinfunction "1_1") (pintype "passive"))
      (node (ref "C87") (pin "1") (pinfunction "1_1") (pintype "passive"))
      (node (ref "C89") (pin "1") (pinfunction "1_1") (pintype "passive"))
      (node (ref "C90") (pin "1") (pinfunction "1_1") (pintype "passive"))
      (node (ref "C91") (pin "1") (pinfunction "1_1") (pintype "passive"))
      (node (ref "C92") (pin "1") (pinfunction "1_1") (pintype "passive"))
      (node (ref "C93") (pin "1") (pinfunction "1_1") (pintype "passive"))
      (node (ref "D21") (pin "2") (pinfunction "K_2") (pintype "passive"))
      (node (ref "D22") (pin "2") (pinfunction "K_2") (pintype "passive"))
      (node (ref "D23") (pin "2") (pinfunction "K_2") (pintype "passive"))
      (node (ref "IC1") (pin "8") (pinfunction "GND_8") (pintype "passive"))
      (node (ref "M1") (pin "2") (pinfunction "GND_2") (pintype "passive"))
      (node (ref "P4") (pin "1") (pinfunction "1_1") (pintype "passive"))
      (node (ref "P6") (pin "2") (pinfunction "2_2") (pintype "passive"))
      (node (ref "P7") (pin "2") (pinfunction "2_2") (pintype "passive"))
      (node (ref "P8") (pin "3") (pinfunction "3_3") (pintype "passive"))
      (node (ref "R182") (pin "1") (pinfunction "1_1") (pintype "passive"))
      (node (ref "U18") (pin "1") (pinfunction "GND_1") (pintype "passive"))
      (node (ref "U19") (pin "15") (pinfunction "VSS_15") (pintype "passive"))
      (node (ref "U19") (pin "31") (pinfunction "AVSS_31") (pintype "passive"))
      (node (ref "U19") (pin "36") (pinfunction "VSS_36") (pintype "passive"))
      (node (ref "U19") (pin "45") (pinfunction "VSS_45") (pintype "passive"))
      (node (ref "U19") (pin "65") (pinfunction "VSS_65") (pintype "passive"))
      (node (ref "U19") (pin "75") (pinfunction "VSS_75") (pintype "passive"))
      (node (ref "U32") (pin "3") (pinfunction "GND_3") (pintype "passive"))
      (node (ref "U33") (pin "3") (pinfunction "GND_3") (pintype "passive"))
      (node (ref "U34") (pin "3") (pinfunction "GND_3") (pintype "passive"))
      (node (ref "U35") (pin "3") (pinfunction "GND_3") (pintype "passive"))
      (node (ref "U36") (pin "3") (pinfunction "GND_3") (pintype "passive"))
      (node (ref "U38") (pin "2") (pinfunction "2_2") (pintype "passive"))
      (node (ref "U39") (pin "2") (pinfunction "2_2") (pintype "passive"))
      (node (ref "U40") (pin "2") (pinfunction "2_2") (pintype "passive"))
      (node (ref "U41") (pin "3") (pinfunction "3_3") (pintype "passive"))
      (node (ref "U42") (pin "2") (pinfunction "2_2") (pintype "passive"))
      (node (ref "U43") (pin "2") (pinfunction "2_2") (pintype "passive"))
      (node (ref "U44") (pin "3") (pinfunction "3_3") (pintype "passive"))
      (node (ref "U45") (pin "2") (pinfunction "2_2") (pintype "passive"))
      (node (ref "U46") (pin "2") (pinfunction "2_2") (pintype "passive"))
      (node (ref "U47") (pin "2") (pinfunction "2_2") (pintype "passive"))
      (node (ref "U48") (pin "3") (pinfunction "3_3") (pintype "passive"))
      (node (ref "U49") (pin "2") (pinfunction "2_2") (pintype "passive"))
      (node (ref "U50") (pin "2") (pinfunction "2_2") (pintype "passive"))
      (node (ref "U51") (pin "2") (pinfunction "2_2") (pintype "passive"))
      (node (ref "U52") (pin "3") (pinfunction "3_3") (pintype "passive"))
      (node (ref "U53") (pin "2") (pinfunction "2_2") (pintype "passive"))
      (node (ref "USB") (pin "4") (pinfunction "GND_4") (pintype "power_in"))
      (node (ref "USB") (pin "6") (pinfunction "SHLD_6") (pintype "passive"))
      (node (ref "USB") (pin "7") (pinfunction "SHLD_7") (pintype "passive"))
      (node (ref "USB") (pin "8") (pinfunction "SHLD_8") (pintype "passive"))
      (node (ref "USB") (pin "9") (pinfunction "SHLD_9") (pintype "passive"))
    )
    (net (code "75") (name "GND_OUT") (class "Default")
      (node (ref "P4") (pin "2") (pinfunction "2_2") (pintype "passive"))
      (node (ref "U38") (pin "3") (pinfunction "3_3") (pintype "passive"))
      (node (ref "U39") (pin "3") (pinfunction "3_3") (pintype "passive"))
      (node (ref "U40") (pin "3") (pinfunction "3_3") (pintype "passive"))
      (node (ref "U41") (pin "2") (pinfunction "2_2") (pintype "passive"))
      (node (ref "U42") (pin "3") (pinfunction "3_3") (pintype "passive"))
      (node (ref "U43") (pin "3") (pinfunction "3_3") (pintype "passive"))
      (node (ref "U44") (pin "2") (pinfunction "2_2") (pintype "passive"))
      (node (ref "U45") (pin "3") (pinfunction "3_3") (pintype "passive"))
      (node (ref "U46") (pin "3") (pinfunction "3_3") (pintype "passive"))
      (node (ref "U47") (pin "3") (pinfunction "3_3") (pintype "passive"))
      (node (ref "U48") (pin "2") (pinfunction "2_2") (pintype "passive"))
      (node (ref "U49") (pin "3") (pinfunction "3_3") (pintype "passive"))
      (node (ref "U50") (pin "3") (pinfunction "3_3") (pintype "passive"))
      (node (ref "U51") (pin "3") (pinfunction "3_3") (pintype "passive"))
      (node (ref "U52") (pin "2") (pinfunction "2_2") (pintype "passive"))
      (node (ref "U53") (pin "3") (pinfunction "3_3") (pintype "passive"))
    )
    (net (code "76") (name "Net-(12M-OSC1)") (class "Default")
      (node (ref "12M") (pin "1") (pinfunction "OSC1_1") (pintype "passive"))
      (node (ref "C86") (pin "2") (pinfunction "2_2") (pintype "passive"))
      (node (ref "IC1") (pin "9") (pinfunction "XI_9") (pintype "passive"))
    )
    (net (code "77") (name "Net-(12M-OSC2)") (class "Default")
      (node (ref "12M") (pin "2") (pinfunction "OSC2_2") (pintype "passive"))
      (node (ref "C87") (pin "2") (pinfunction "2_2") (pintype "passive"))
      (node (ref "IC1") (pin "10") (pinfunction "XO_10") (pintype "passive"))
    )
    (net (code "78") (name "Net-(C80-Pad1)") (class "Default")
      (node (ref "C80") (pin "1") (pinfunction "1_1") (pintype "passive"))
      (node (ref "R7") (pin "2") (pinfunction "2_2") (pintype "passive"))
      (node (ref "R8") (pin "2") (pinfunction "2_2") (pintype "passive"))
    )
    (net (code "79") (name "Net-(D21-A)") (class "Default")
      (node (ref "D21") (pin "1") (pinfunction "A_1") (pintype "passive"))
      (node (ref "R14") (pin "2") (pinfunction "2_2") (pintype "passive"))
    )
    (net (code "80") (name "Net-(D22-A)") (class "Default")
      (node (ref "D22") (pin "1") (pinfunction "A_1") (pintype "passive"))
      (node (ref "R161") (pin "2") (pinfunction "2_2") (pintype "passive"))
    )
    (net (code "81") (name "Net-(D23-A)") (class "Default")
      (node (ref "D23") (pin "1") (pinfunction "A_1") (pintype "passive"))
      (node (ref "R162") (pin "2") (pinfunction "2_2") (pintype "passive"))
    )
    (net (code "82") (name "Net-(IC1-V3)") (class "Default")
      (node (ref "C83") (pin "2") (pinfunction "2_2") (pintype "passive"))
      (node (ref "IC1") (pin "5") (pinfunction "V3_5") (pintype "passive"))
    )
    (net (code "83") (name "Net-(M1-CANG)") (class "Default")
      (node (ref "M1") (pin "8") (pinfunction "CANG_8") (pintype "passive"))
      (node (ref "P3") (pin "1") (pinfunction "1_1") (pintype "passive"))
      (node (ref "P3") (pin "2") (pinfunction "2_2") (pintype "passive"))
    )
    (net (code "84") (name "Net-(M1-CANH)") (class "Default")
      (node (ref "M1") (pin "6") (pinfunction "CANH_6") (pintype "passive"))
      (node (ref "P3") (pin "5") (pinfunction "5_5") (pintype "passive"))
      (node (ref "P3") (pin "6") (pinfunction "6_6") (pintype "passive"))
      (node (ref "R136") (pin "1") (pinfunction "1_1") (pintype "passive"))
    )
    (net (code "85") (name "Net-(M1-CANL)") (class "Default")
      (node (ref "M1") (pin "7") (pinfunction "CANL_7") (pintype "passive"))
      (node (ref "P3") (pin "3") (pinfunction "3_3") (pintype "passive"))
      (node (ref "P3") (pin "4") (pinfunction "4_4") (pintype "passive"))
      (node (ref "R136") (pin "2") (pinfunction "2_2") (pintype "passive"))
    )
    (net (code "86") (name "Net-(M1-RXD)") (class "Default")
      (node (ref "M1") (pin "4") (pinfunction "RXD_4") (pintype "passive"))
      (node (ref "R138") (pin "2") (pinfunction "2_2") (pintype "passive"))
      (node (ref "R139") (pin "2") (pinfunction "2_2") (pintype "passive"))
    )
    (net (code "87") (name "Net-(M1-TXD)") (class "Default")
      (node (ref "M1") (pin "3") (pinfunction "TXD_3") (pintype "passive"))
      (node (ref "R135") (pin "2") (pinfunction "2_2") (pintype "passive"))
      (node (ref "R137") (pin "2") (pinfunction "2_2") (pintype "passive"))
    )
    (net (code "88") (name "Net-(P8-Pad2)") (class "Default")
      (node (ref "P8") (pin "2") (pinfunction "2_2") (pintype "passive"))
      (node (ref "R22") (pin "1") (pinfunction "1_1") (pintype "passive"))
    )
    (net (code "89") (name "Net-(R153-Pad1)") (class "Default")
      (node (ref "R153") (pin "1") (pinfunction "1_1") (pintype "passive"))
      (node (ref "U44") (pin "1") (pinfunction "1_1") (pintype "passive"))
    )
    (net (code "90") (name "Net-(R154-Pad1)") (class "Default")
      (node (ref "R154") (pin "1") (pinfunction "1_1") (pintype "passive"))
      (node (ref "U41") (pin "1") (pinfunction "1_1") (pintype "passive"))
    )
    (net (code "91") (name "Net-(R155-Pad1)") (class "Default")
      (node (ref "R155") (pin "1") (pinfunction "1_1") (pintype "passive"))
      (node (ref "U52") (pin "1") (pinfunction "1_1") (pintype "passive"))
    )
    (net (code "92") (name "Net-(R156-Pad1)") (class "Default")
      (node (ref "R156") (pin "1") (pinfunction "1_1") (pintype "passive"))
      (node (ref "U48") (pin "1") (pinfunction "1_1") (pintype "passive"))
    )
    (net (code "93") (name "Net-(U19-CORE)") (class "Default")
      (node (ref "C79") (pin "1") (pinfunction "1_1") (pintype "passive"))
      (node (ref "U19") (pin "85") (pinfunction "CORE_85") (pintype "passive"))
    )
    (net (code "94") (name "Net-(U19-RA6)") (class "Default")
      (node (ref "R132") (pin "2") (pinfunction "2_2") (pintype "passive"))
      (node (ref "U19") (pin "91") (pinfunction "RA6_91") (pintype "passive"))
    )
    (net (code "95") (name "Net-(U19-RA7)") (class "Default")
      (node (ref "R131") (pin "2") (pinfunction "2_2") (pintype "passive"))
      (node (ref "U19") (pin "92") (pinfunction "RA7_92") (pintype "passive"))
    )
    (net (code "96") (name "Net-(U19-RD2)") (class "Default")
      (node (ref "R134") (pin "2") (pinfunction "2_2") (pintype "passive"))
      (node (ref "U19") (pin "77") (pinfunction "RD2_77") (pintype "passive"))
    )
    (net (code "97") (name "Net-(U19-RD3)") (class "Default")
      (node (ref "R133") (pin "2") (pinfunction "2_2") (pintype "passive"))
      (node (ref "U19") (pin "78") (pinfunction "RD3_78") (pintype "passive"))
    )
    (net (code "98") (name "Net-(U19-RE0)") (class "Default")
      (node (ref "A19") (pin "7") (pinfunction "7_7") (pintype "passive"))
      (node (ref "U19") (pin "93") (pinfunction "RE0_93") (pintype "passive"))
    )
    (net (code "99") (name "Net-(U19-RE1)") (class "Default")
      (node (ref "A19") (pin "5") (pinfunction "5_5") (pintype "passive"))
      (node (ref "U19") (pin "94") (pinfunction "RE1_94") (pintype "passive"))
    )
    (net (code "100") (name "Net-(U19-RE2)") (class "Default")
      (node (ref "A18") (pin "5") (pinfunction "5_5") (pintype "passive"))
      (node (ref "U19") (pin "98") (pinfunction "RE2_98") (pintype "passive"))
    )
    (net (code "101") (name "Net-(U19-RE3)") (class "Default")
      (node (ref "A18") (pin "3") (pinfunction "3_3") (pintype "passive"))
      (node (ref "U19") (pin "99") (pinfunction "RE3_99") (pintype "passive"))
    )
    (net (code "102") (name "Net-(U19-RE4)") (class "Default")
      (node (ref "A18") (pin "1") (pinfunction "1_1") (pintype "passive"))
      (node (ref "U19") (pin "100") (pinfunction "RE4_100") (pintype "passive"))
    )
    (net (code "103") (name "Net-(U19-RG12)") (class "Default")
      (node (ref "A19") (pin "1") (pinfunction "1_1") (pintype "passive"))
      (node (ref "U19") (pin "96") (pinfunction "RG12_96") (pintype "passive"))
    )
    (net (code "104") (name "Net-(U19-RG13)") (class "Default")
      (node (ref "A18") (pin "7") (pinfunction "7_7") (pintype "passive"))
      (node (ref "U19") (pin "97") (pinfunction "RG13_97") (pintype "passive"))
    )
    (net (code "105") (name "Net-(U19-RG14)") (class "Default")
      (node (ref "A19") (pin "3") (pinfunction "3_3") (pintype "passive"))
      (node (ref "U19") (pin "95") (pinfunction "RG14_95") (pintype "passive"))
    )
    (net (code "106") (name "Net-(U19-VBUS)") (class "Default")
      (node (ref "R176") (pin "1") (pinfunction "1_1") (pintype "passive"))
      (node (ref "U19") (pin "54") (pinfunction "VBUS_54") (pintype "passive"))
    )
    (net (code "107") (name "Net-(U19-VUSB)") (class "Default")
      (node (ref "R174") (pin "1") (pinfunction "1_1") (pintype "passive"))
      (node (ref "U19") (pin "55") (pinfunction "VUSB_55") (pintype "passive"))
    )
    (net (code "108") (name "USB_5V") (class "Default")
      (node (ref "C89") (pin "2") (pinfunction "2_2") (pintype "passive"))
      (node (ref "C91") (pin "2") (pinfunction "2_2") (pintype "passive"))
      (node (ref "C92") (pin "2") (pinfunction "2_2") (pintype "passive"))
      (node (ref "C93") (pin "2") (pinfunction "2_2") (pintype "passive"))
      (node (ref "USB") (pin "1") (pinfunction "VBUS_1") (pintype "power_in"))
    )
    (net (code "109") (name "VCC_OUT") (class "Default")
      (node (ref "P4") (pin "4") (pinfunction "4_4") (pintype "passive"))
      (node (ref "R140") (pin "2") (pinfunction "2_2") (pintype "passive"))
      (node (ref "R141") (pin "2") (pinfunction "2_2") (pintype "passive"))
      (node (ref "R142") (pin "2") (pinfunction "2_2") (pintype "passive"))
      (node (ref "R143") (pin "2") (pinfunction "2_2") (pintype "passive"))
      (node (ref "R144") (pin "2") (pinfunction "2_2") (pintype "passive"))
      (node (ref "R145") (pin "2") (pinfunction "2_2") (pintype "passive"))
      (node (ref "R146") (pin "2") (pinfunction "2_2") (pintype "passive"))
      (node (ref "R147") (pin "2") (pinfunction "2_2") (pintype "passive"))
      (node (ref "R148") (pin "2") (pinfunction "2_2") (pintype "passive"))
      (node (ref "R149") (pin "2") (pinfunction "2_2") (pintype "passive"))
      (node (ref "R151") (pin "2") (pinfunction "2_2") (pintype "passive"))
      (node (ref "R152") (pin "2") (pinfunction "2_2") (pintype "passive"))
    )
    (net (code "110") (name "unconnected-(IC1-ACT#-Pad2)") (class "Default")
      (node (ref "IC1") (pin "2") (pinfunction "ACT#_2") (pintype "passive"))
    )
    (net (code "111") (name "unconnected-(IC1-CKO-Pad1)") (class "Default")
      (node (ref "IC1") (pin "1") (pinfunction "CKO_1") (pintype "passive"))
    )
    (net (code "112") (name "unconnected-(IC1-CTS#-Pad11)") (class "Default")
      (node (ref "IC1") (pin "11") (pinfunction "CTS#_11") (pintype "passive"))
    )
    (net (code "113") (name "unconnected-(IC1-DCD#-Pad14)") (class "Default")
      (node (ref "IC1") (pin "14") (pinfunction "DCD#_14") (pintype "passive"))
    )
    (net (code "114") (name "unconnected-(IC1-DSR#-Pad12)") (class "Default")
      (node (ref "IC1") (pin "12") (pinfunction "DSR#_12") (pintype "passive"))
    )
    (net (code "115") (name "unconnected-(IC1-DTR#-Pad15)") (class "Default")
      (node (ref "IC1") (pin "15") (pinfunction "DTR#_15") (pintype "passive"))
    )
    (net (code "116") (name "unconnected-(IC1-NC.-Pad17)") (class "Default")
      (node (ref "IC1") (pin "17") (pinfunction "NC._17") (pintype "passive"))
    )
    (net (code "117") (name "unconnected-(IC1-NOS#-Pad20)") (class "Default")
      (node (ref "IC1") (pin "20") (pinfunction "NOS#_20") (pintype "passive"))
    )
    (net (code "118") (name "unconnected-(IC1-R232-Pad18)") (class "Default")
      (node (ref "IC1") (pin "18") (pinfunction "R232_18") (pintype "passive"))
    )
    (net (code "119") (name "unconnected-(IC1-RI#-Pad13)") (class "Default")
      (node (ref "IC1") (pin "13") (pinfunction "RI#_13") (pintype "passive"))
    )
    (net (code "120") (name "unconnected-(IC1-RTS#-Pad16)") (class "Default")
      (node (ref "IC1") (pin "16") (pinfunction "RTS#_16") (pintype "passive"))
    )
    (net (code "121") (name "unconnected-(P8-Pad6)") (class "Default")
      (node (ref "P8") (pin "6") (pinfunction "6_6") (pintype "passive"))
    )
    (net (code "122") (name "unconnected-(U19-D+{slash}RG2-Pad57)") (class "Default")
      (node (ref "U19") (pin "57") (pinfunction "D+/RG2_57") (pintype "passive"))
    )
    (net (code "123") (name "unconnected-(U19-D-{slash}RG3-Pad56)") (class "Default")
      (node (ref "U19") (pin "56") (pinfunction "D-/RG3_56") (pintype "passive"))
    )
    (net (code "124") (name "unconnected-(U19-IC5{slash}RD12-Pad79)") (class "Default")
      (node (ref "U19") (pin "79") (pinfunction "IC5/RD12_79") (pintype "passive"))
    )
    (net (code "125") (name "unconnected-(U19-IC6{slash}RD13-Pad80)") (class "Default")
      (node (ref "U19") (pin "80") (pinfunction "IC6/RD13_80") (pintype "passive"))
    )
    (net (code "126") (name "unconnected-(U19-INT3{slash}RA14-Pad66)") (class "Default")
      (node (ref "U19") (pin "66") (pinfunction "INT3/RA14_66") (pintype "passive"))
    )
    (net (code "127") (name "unconnected-(U19-INT4{slash}RA15-Pad67)") (class "Default")
      (node (ref "U19") (pin "67") (pinfunction "INT4/RA15_67") (pintype "passive"))
    )
    (net (code "128") (name "unconnected-(U19-RA0{slash}TMS-Pad17)") (class "Default")
      (node (ref "U19") (pin "17") (pinfunction "RA0/TMS_17") (pintype "passive"))
    )
    (net (code "129") (name "unconnected-(U19-RA1{slash}TCK-Pad38)") (class "Default")
      (node (ref "U19") (pin "38") (pinfunction "RA1/TCK_38") (pintype "passive"))
    )
    (net (code "130") (name "unconnected-(U19-RA9{slash}VREF--Pad28)") (class "Default")
      (node (ref "U19") (pin "28") (pinfunction "RA9/VREF-_28") (pintype "passive"))
    )
    (net (code "131") (name "unconnected-(U19-RA10{slash}VREF+-Pad29)") (class "Default")
      (node (ref "U19") (pin "29") (pinfunction "RA10/VREF+_29") (pintype "passive"))
    )
    (net (code "132") (name "unconnected-(U19-RB2{slash}CN4-Pad23)") (class "Default")
      (node (ref "U19") (pin "23") (pinfunction "RB2/CN4_23") (pintype "passive"))
    )
    (net (code "133") (name "unconnected-(U19-RB3{slash}CN5-Pad22)") (class "Default")
      (node (ref "U19") (pin "22") (pinfunction "RB3/CN5_22") (pintype "passive"))
    )
    (net (code "134") (name "unconnected-(U19-RB6{slash}PGC2-Pad26)") (class "Default")
      (node (ref "U19") (pin "26") (pinfunction "RB6/PGC2_26") (pintype "passive"))
    )
    (net (code "135") (name "unconnected-(U19-RB7{slash}PGD2-Pad27)") (class "Default")
      (node (ref "U19") (pin "27") (pinfunction "RB7/PGD2_27") (pintype "passive"))
    )
    (net (code "136") (name "unconnected-(U19-RB11-Pad35)") (class "Default")
      (node (ref "U19") (pin "35") (pinfunction "RB11_35") (pintype "passive"))
    )
    (net (code "137") (name "unconnected-(U19-RB12-Pad41)") (class "Default")
      (node (ref "U19") (pin "41") (pinfunction "RB12_41") (pintype "passive"))
    )
    (net (code "138") (name "unconnected-(U19-RB13-Pad42)") (class "Default")
      (node (ref "U19") (pin "42") (pinfunction "RB13_42") (pintype "passive"))
    )
    (net (code "139") (name "unconnected-(U19-RC3-Pad8)") (class "Default")
      (node (ref "U19") (pin "8") (pinfunction "RC3_8") (pintype "passive"))
    )
    (net (code "140") (name "unconnected-(U19-RC4-Pad9)") (class "Default")
      (node (ref "U19") (pin "9") (pinfunction "RC4_9") (pintype "passive"))
    )
    (net (code "141") (name "unconnected-(U19-RD4-Pad81)") (class "Default")
      (node (ref "U19") (pin "81") (pinfunction "RD4_81") (pintype "passive"))
    )
    (net (code "142") (name "unconnected-(U19-RD5-Pad82)") (class "Default")
      (node (ref "U19") (pin "82") (pinfunction "RD5_82") (pintype "passive"))
    )
    (net (code "143") (name "unconnected-(U19-RD14{slash}U4RX-Pad47)") (class "Default")
      (node (ref "U19") (pin "47") (pinfunction "RD14/U4RX_47") (pintype "passive"))
    )
    (net (code "144") (name "unconnected-(U19-RE5-Pad3)") (class "Default")
      (node (ref "U19") (pin "3") (pinfunction "RE5_3") (pintype "passive"))
    )
    (net (code "145") (name "unconnected-(U19-RE6-Pad4)") (class "Default")
      (node (ref "U19") (pin "4") (pinfunction "RE6_4") (pintype "passive"))
    )
    (net (code "146") (name "unconnected-(U19-RE7-Pad5)") (class "Default")
      (node (ref "U19") (pin "5") (pinfunction "RE7_5") (pintype "passive"))
    )
    (net (code "147") (name "unconnected-(U19-RE8{slash}INT1-Pad18)") (class "Default")
      (node (ref "U19") (pin "18") (pinfunction "RE8/INT1_18") (pintype "passive"))
    )
    (net (code "148") (name "unconnected-(U19-RE9{slash}INT2-Pad19)") (class "Default")
      (node (ref "U19") (pin "19") (pinfunction "RE9/INT2_19") (pintype "passive"))
    )
    (net (code "149") (name "unconnected-(U19-RG9{slash}~{SS2}-Pad14)") (class "Default")
      (node (ref "U19") (pin "14") (pinfunction "RG9/~{SS2}_14") (pintype "passive"))
    )
    (net (code "150") (name "unconnected-(U19-RG15-Pad1)") (class "Default")
      (node (ref "U19") (pin "1") (pinfunction "RG15_1") (pintype "passive"))
    )
    (net (code "151") (name "unconnected-(U19-SOSCI{slash}RC13-Pad73)") (class "Default")
      (node (ref "U19") (pin "73") (pinfunction "SOSCI/RC13_73") (pintype "passive"))
    )
    (net (code "152") (name "unconnected-(U19-SOSCO{slash}RC14-Pad74)") (class "Default")
      (node (ref "U19") (pin "74") (pinfunction "SOSCO/RC14_74") (pintype "passive"))
    )
    (net (code "153") (name "unconnected-(U19-TDI{slash}RA4-Pad60)") (class "Default")
      (node (ref "U19") (pin "60") (pinfunction "TDI/RA4_60") (pintype "passive"))
    )
    (net (code "154") (name "unconnected-(U19-TDO{slash}RA5-Pad61)") (class "Default")
      (node (ref "U19") (pin "61") (pinfunction "TDO/RA5_61") (pintype "passive"))
    )
    (net (code "155") (name "unconnected-(U19-U1TX{slash}RF8-Pad53)") (class "Default")
      (node (ref "U19") (pin "53") (pinfunction "U1TX/RF8_53") (pintype "passive"))
    )
    (net (code "156") (name "unconnected-(U19-USBID{slash}RF3-Pad51)") (class "Default")
      (node (ref "U19") (pin "51") (pinfunction "USBID/RF3_51") (pintype "passive"))
    )
    (net (code "157") (name "unconnected-(U36-NC-Pad1)") (class "Default")
      (node (ref "U36") (pin "1") (pinfunction "NC_1") (pintype "passive"))
    )
    (net (code "158") (name "unconnected-(USB-SHLD-Pad5)") (class "Default")
      (node (ref "USB") (pin "5") (pinfunction "SHLD_5") (pintype "passive"))
    )
  )
)
